# sub-unit-psu.net
KiCad netlist of a schematic drawn in EAGLE
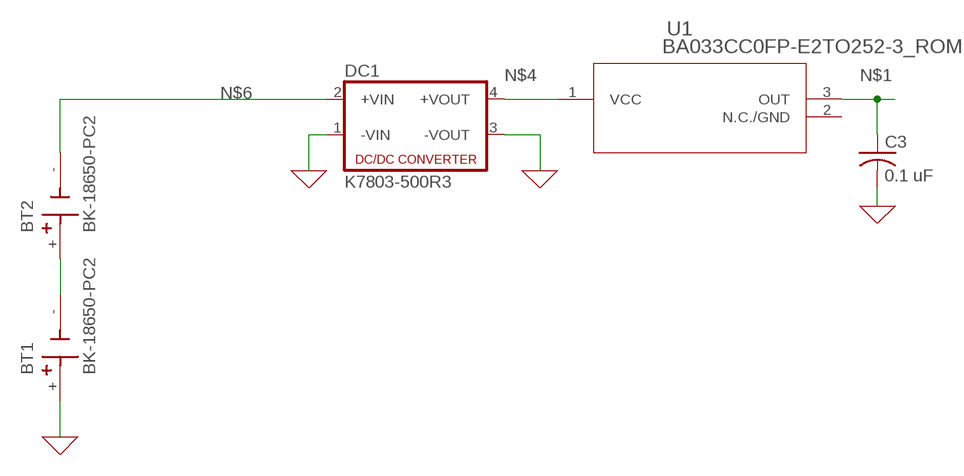
[diagram p0: schematic, sheet 1]

(export (version "E")
  (design (tool "Eeschema 10.0.6"))
  (components
    (comp (ref "BT1")
      (value "BK-18650-PC2")
      (footprint "eagle-import:BAT_BK-18650-PC2")
      (fields (field (name "MF") "MPD (Memory Protection Devices)"))
      (libsource (lib "eagle-import") (part "BK-18650-PC2"))
    )
    (comp (ref "BT2")
      (value "BK-18650-PC2")
      (footprint "eagle-import:BAT_BK-18650-PC2")
      (fields (field (name "MF") "MPD (Memory Protection Devices)"))
      (libsource (lib "eagle-import") (part "BK-18650-PC2"))
    )
    (comp (ref "C3")
      (value "0.1 uF")
      (footprint "eagle-import:C050-024X044")
      (libsource (lib "eagle-import") (part "C-US050-024X044"))
    )
    (comp (ref "DC1")
      (value "K7803-500R3")
      (footprint "eagle-import:NME")
      (fields (field (name "MF") "C & D TECHNOLOGIES, INC") (field (name "MPN") "NME1205D"))
      (libsource (lib "eagle-import") (part "NME"))
    )
    (comp (ref "U1")
      (value "BA033CC0FP-E2TO252-3_ROM")
      (footprint "eagle-import:TO252-3_ROM")
      (fields
        (field (name "MANUFACTURER_PART_NUMBER") "BA033CC0FP-E2")
        (field (name "COPYRIGHT") "Copyright (C) 2023 Ultra Librarian. All rights reserved.")
      )
      (libsource (lib "eagle-import") (part "BA033CC0FP-E2TO252-3_ROM"))
    )
  )
  (nets
    (net (code "1") (name "/N$1") (class "Default")
      (node (ref "C3") (pin "1") (pinfunction "1_1") (pintype "passive"))
      (node (ref "U1") (pin "3") (pinfunction "OUT_3") (pintype "output"))
    )
    (net (code "2") (name "/N$4") (class "Default")
      (node (ref "DC1") (pin "4") (pinfunction "+VOUT_4") (pintype "passive"))
      (node (ref "U1") (pin "1") (pinfunction "VCC_1") (pintype "power_in"))
    )
    (net (code "3") (name "/N$6") (class "Default")
      (node (ref "BT2") (pin "-") (pinfunction "-_-") (pintype "passive"))
      (node (ref "DC1") (pin "2") (pinfunction "+VIN_2") (pintype "passive"))
    )
    (net (code "4") (name "GND") (class "Default")
      (node (ref "BT1") (pin "+") (pinfunction "+_+") (pintype "passive"))
      (node (ref "C3") (pin "2") (pinfunction "2_2") (pintype "passive"))
      (node (ref "DC1") (pin "1") (pinfunction "-VIN_1") (pintype "passive"))
      (node (ref "DC1") (pin "3") (pinfunction "-VOUT_3") (pintype "passive"))
    )
    (net (code "5") (name "Net-(BT1-Pad-)") (class "Default")
      (node (ref "BT1") (pin "-") (pinfunction "-_-") (pintype "passive"))
      (node (ref "BT2") (pin "+") (pinfunction "+_+") (pintype "passive"))
    )
    (net (code "6") (name "unconnected-(U1-N.C.{slash}GND-Pad2)") (class "Default")
      (node (ref "U1") (pin "2") (pinfunction "N.C./GND_2") (pintype "no_connect"))
    )
  )
)
